# EPS_Battery_Controller_Current-Meas.net
KiCad netlist of a schematic drawn in Altium Designer
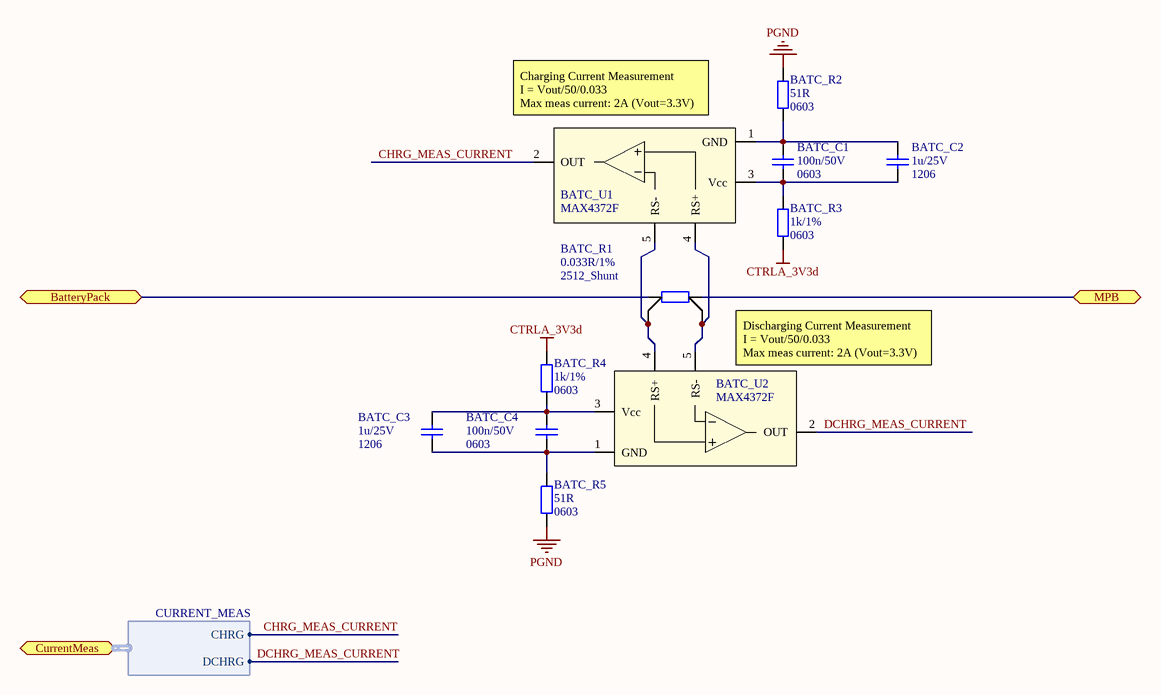
[diagram p0: EPS_Battery_Controller_Current-Meas.SchDoc]

(export (version "E")
  (design (tool "Eeschema 10.0.6"))
  (components
    (comp (ref "BATC_C1")
      (value "100n/50V")
      (footprint "SMD_Capacitor_0603")
      (description "Ceramic Cap Murata Automotive 100n/50V X7R 0603")
      (fields
        (field (name "MANUFACTURER") "Murata")
        (field (name "MANUFACTURERPARTNUMBER") "GCJ188R71H104KA12D")
        (field (name "PACKAGE") "0603")
      )
      (libsource (lib "capacitors") (part "Cer_GCJ188R71H104KA12D"))
    )
    (comp (ref "BATC_C2")
      (value "1u/25V")
      (footprint "SMD_Capacitor_1206")
      (description "Ceramic Cap Kemet COTS 1u/25V X7R 1206")
      (fields
        (field (name "MANUFACTURERPARTNUMBER") "C1206T105K3RALTU")
        (field (name "MANUFACTURER") "Kemet")
        (field (name "PACKAGE") "1206")
      )
      (libsource (lib "capacitors") (part "Cer_C1206T105K3RALTU"))
    )
    (comp (ref "BATC_C3")
      (value "1u/25V")
      (footprint "SMD_Capacitor_1206")
      (description "Ceramic Cap Kemet COTS 1u/25V X7R 1206")
      (fields
        (field (name "MANUFACTURERPARTNUMBER") "C1206T105K3RALTU")
        (field (name "MANUFACTURER") "Kemet")
        (field (name "PACKAGE") "1206")
      )
      (libsource (lib "capacitors") (part "Cer_C1206T105K3RALTU"))
    )
    (comp (ref "BATC_C4")
      (value "100n/50V")
      (footprint "SMD_Capacitor_0603")
      (description "Ceramic Cap Murata Automotive 100n/50V X7R 0603")
      (fields
        (field (name "MANUFACTURER") "Murata")
        (field (name "MANUFACTURERPARTNUMBER") "GCJ188R71H104KA12D")
        (field (name "PACKAGE") "0603")
      )
      (libsource (lib "capacitors") (part "Cer_GCJ188R71H104KA12D"))
    )
    (comp (ref "BATC_R1")
      (value "0.033R/1%")
      (footprint "SMD_Resistor-shunt_2512")
      (description "33mR ,1%, 2W, shunt resistor, TE Connectivity.")
      (fields
        (field (name "MANUFACTURERPARTNUMBER") "LR2512-R033FW")
        (field (name "MANUFACTURER") "TE Connectivity")
        (field (name "PACKAGE") "2512_Shunt")
      )
      (libsource (lib "resistors") (part "LR2512-R033FW"))
    )
    (comp (ref "BATC_R2")
      (value "51R")
      (footprint "SMD_Resistor_0603")
      (fields (field (name "PACKAGE") "0603"))
      (libsource (lib "") (part "Res_1"))
    )
    (comp (ref "BATC_R3")
      (value "1k/1%")
      (footprint "SMD_Resistor_0603")
      (fields (field (name "PACKAGE") "0603"))
      (libsource (lib "") (part "Res_1"))
    )
    (comp (ref "BATC_R4")
      (value "1k/1%")
      (footprint "SMD_Resistor_0603")
      (fields (field (name "PACKAGE") "0603"))
      (libsource (lib "resistors") (part "Res"))
    )
    (comp (ref "BATC_R5")
      (value "51R")
      (footprint "SMD_Resistor_0603")
      (fields (field (name "PACKAGE") "0603"))
      (libsource (lib "") (part "Res_1"))
    )
    (comp (ref "BATC_U1")
      (value "MAX4372F")
      (footprint "SOT23-5")
      (description "High-Side Current-Sense Amplifier with Voltage Output")
      (fields (field (name "MANUFACTURER") "Maxim Integrated Products"))
      (libsource (lib "microcircuits") (part "MAX4372"))
    )
    (comp (ref "BATC_U2")
      (value "MAX4372F")
      (footprint "SOT23-5")
      (description "High-Side Current-Sense Amplifier with Voltage Output")
      (fields (field (name "MANUFACTURER") "Maxim Integrated Products"))
      (libsource (lib "") (part "MAX4372_1"))
    )
  )
  (nets
    (net (code "2") (name "/BatteryPack") (class "Default")
      (node (ref "BATC_R1") (pin "1") (pinfunction "1_1") (pintype "passive"))
    )
    (net (code "3") (name "/CHRG_MEAS_CURRENT") (class "Default")
      (node (ref "BATC_U1") (pin "2") (pinfunction "OUT_2") (pintype "passive"))
    )
    (net (code "4") (name "/DCHRG_MEAS_CURRENT") (class "Default")
      (node (ref "BATC_U2") (pin "2") (pinfunction "OUT_2") (pintype "passive"))
    )
    (net (code "5") (name "/MPB") (class "Default")
      (node (ref "BATC_R1") (pin "4") (pinfunction "4_4") (pintype "passive"))
    )
    (net (code "7") (name "CTRLA_3V3d") (class "Default")
      (node (ref "BATC_R3") (pin "1") (pinfunction "1_1") (pintype "passive"))
      (node (ref "BATC_R4") (pin "1") (pinfunction "1_1") (pintype "passive"))
    )
    (net (code "8") (name "Net-(BATC_U1-GND)") (class "Default")
      (node (ref "BATC_C1") (pin "1") (pinfunction "1_1") (pintype "passive"))
      (node (ref "BATC_C2") (pin "1") (pinfunction "1_1") (pintype "passive"))
      (node (ref "BATC_R2") (pin "1") (pinfunction "1_1") (pintype "passive"))
      (node (ref "BATC_U1") (pin "1") (pinfunction "GND_1") (pintype "passive"))
    )
    (net (code "9") (name "Net-(BATC_U1-RS+)") (class "Default")
      (node (ref "BATC_R1") (pin "3") (pinfunction "3_3") (pintype "passive"))
      (node (ref "BATC_U1") (pin "4") (pinfunction "RS+_4") (pintype "passive"))
      (node (ref "BATC_U2") (pin "5") (pinfunction "RS-_5") (pintype "passive"))
    )
    (net (code "10") (name "Net-(BATC_U1-RS-)") (class "Default")
      (node (ref "BATC_R1") (pin "2") (pinfunction "2_2") (pintype "passive"))
      (node (ref "BATC_U1") (pin "5") (pinfunction "RS-_5") (pintype "passive"))
      (node (ref "BATC_U2") (pin "4") (pinfunction "RS+_4") (pintype "passive"))
    )
    (net (code "11") (name "Net-(BATC_U1-Vcc)") (class "Default")
      (node (ref "BATC_C1") (pin "2") (pinfunction "2_2") (pintype "passive"))
      (node (ref "BATC_C2") (pin "2") (pinfunction "2_2") (pintype "passive"))
      (node (ref "BATC_R3") (pin "2") (pinfunction "2_2") (pintype "passive"))
      (node (ref "BATC_U1") (pin "3") (pinfunction "Vcc_3") (pintype "passive"))
    )
    (net (code "12") (name "Net-(BATC_U2-GND)") (class "Default")
      (node (ref "BATC_C3") (pin "2") (pinfunction "2_2") (pintype "passive"))
      (node (ref "BATC_C4") (pin "2") (pinfunction "2_2") (pintype "passive"))
      (node (ref "BATC_R5") (pin "2") (pinfunction "2_2") (pintype "passive"))
      (node (ref "BATC_U2") (pin "1") (pinfunction "GND_1") (pintype "passive"))
    )
    (net (code "13") (name "Net-(BATC_U2-Vcc)") (class "Default")
      (node (ref "BATC_C3") (pin "1") (pinfunction "1_1") (pintype "passive"))
      (node (ref "BATC_C4") (pin "1") (pinfunction "1_1") (pintype "passive"))
      (node (ref "BATC_R4") (pin "2") (pinfunction "2_2") (pintype "passive"))
      (node (ref "BATC_U2") (pin "3") (pinfunction "Vcc_3") (pintype "passive"))
    )
    (net (code "14") (name "PGND") (class "Default")
      (node (ref "BATC_R2") (pin "2") (pinfunction "2_2") (pintype "passive"))
      (node (ref "BATC_R5") (pin "1") (pinfunction "1_1") (pintype "passive"))
    )
  )
)
